# MainBoard.net
KiCad netlist of a schematic drawn in Altium Designer
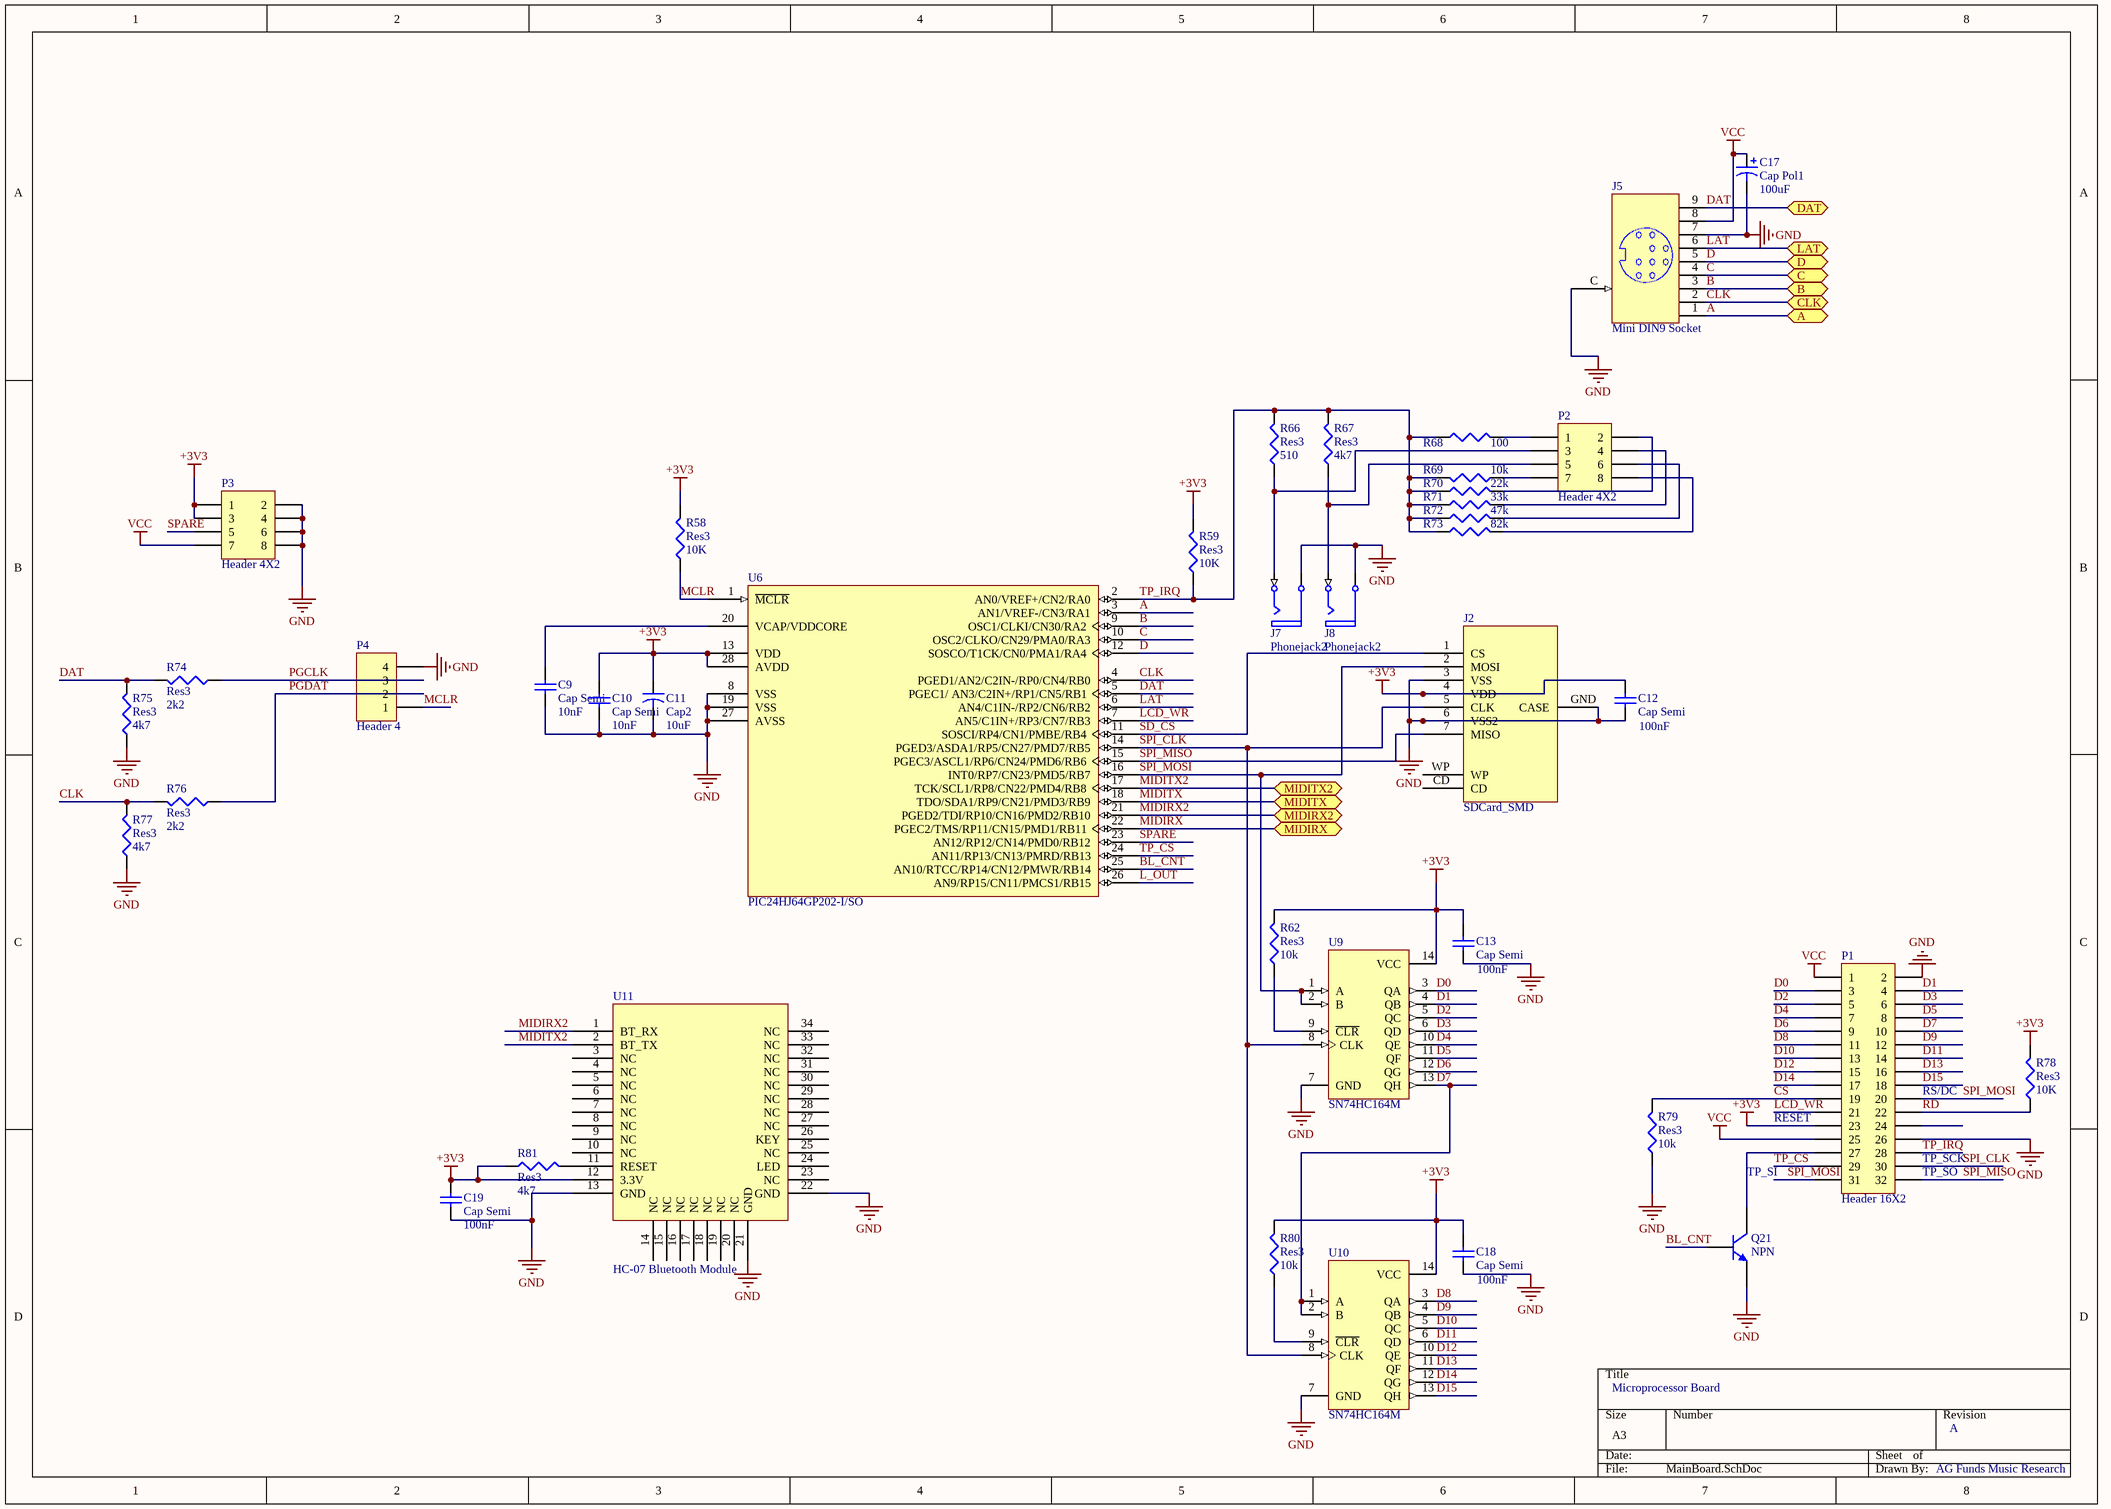
[diagram p0: MainBoard.SchDoc]

(export (version "E")
  (design (tool "Eeschema 10.0.6"))
  (components
    (comp (ref "C9")
      (value "Cap Semi")
      (footprint "1608[0603]")
      (description "Capacitor (Semiconductor SIM Model)")
      (fields (field (name "ALTIUM_VALUE") "10nF") (field (name "PUBLISHER") "Altium Limited"))
      (libsource (lib "Miscellaneous Devices") (part "Cap Semi"))
    )
    (comp (ref "C10")
      (value "Cap Semi")
      (footprint "1608[0603]")
      (description "Capacitor (Semiconductor SIM Model)")
      (fields (field (name "ALTIUM_VALUE") "10nF") (field (name "PUBLISHER") "Altium Limited"))
      (libsource (lib "Miscellaneous Devices") (part "Cap Semi"))
    )
    (comp (ref "C11")
      (value "Cap2")
      (footprint "CAPR5-4X5")
      (description "Capacitor")
      (fields (field (name "ALTIUM_VALUE") "10uF") (field (name "PUBLISHER") "Altium Limited"))
      (libsource (lib "Miscellaneous Devices") (part "Cap2"))
    )
    (comp (ref "C12")
      (value "Cap Semi")
      (footprint "1608[0603]")
      (description "Capacitor (Semiconductor SIM Model)")
      (fields (field (name "ALTIUM_VALUE") "100nF") (field (name "PUBLISHER") "Altium Limited"))
      (libsource (lib "Miscellaneous Devices") (part "Cap Semi"))
    )
    (comp (ref "C13")
      (value "Cap Semi")
      (footprint "1608[0603]")
      (description "Capacitor (Semiconductor SIM Model)")
      (fields (field (name "ALTIUM_VALUE") "100nF") (field (name "PUBLISHER") "Altium Limited"))
      (libsource (lib "Miscellaneous Devices") (part "Cap Semi"))
    )
    (comp (ref "C17")
      (value "Cap Pol1")
      (footprint "RB7.6-15")
      (description "Polarized Capacitor (Radial)")
      (fields (field (name "ALTIUM_VALUE") "100uF") (field (name "PUBLISHER") "Altium Limited"))
      (libsource (lib "Miscellaneous Devices") (part "Cap Pol1"))
    )
    (comp (ref "C18")
      (value "Cap Semi")
      (footprint "1608[0603]")
      (description "Capacitor (Semiconductor SIM Model)")
      (fields (field (name "ALTIUM_VALUE") "100nF") (field (name "PUBLISHER") "Altium Limited"))
      (libsource (lib "Miscellaneous Devices") (part "Cap Semi"))
    )
    (comp (ref "C19")
      (value "Cap Semi")
      (footprint "1608[0603]")
      (description "Capacitor (Semiconductor SIM Model)")
      (fields (field (name "ALTIUM_VALUE") "100nF") (field (name "PUBLISHER") "Altium Limited"))
      (libsource (lib "Miscellaneous Devices") (part "Cap Semi"))
    )
    (comp (ref "J2")
      (value "SDCard_SMD")
      (footprint "SDCard")
      (description "(101-00313) SD-Card Socket Surface Mount Amphenol Shouhmin Industry")
      (libsource (lib "MIDIPiano_7") (part "SDCard_SPI"))
    )
    (comp (ref "J5")
      (value "Mini DIN9 Socket")
      (footprint "RGBLED:9miniDIN")
      (description "CUI Inc. MD-90S MINIDIN9 PCB Mount Socket")
      (fields (field (name "PUBLISHER") "Altium Limited"))
      (libsource (lib "MIDIPiano_7") (part "mDIN9"))
    )
    (comp (ref "J7")
      (value "Phonejack2")
      (footprint "RN111PC")
      (description "Switchcraft RN-111PC Jack Socket, 1/4\" [6.5mm], Thru-Hole, 2-Conductor Open Circuit")
      (fields (field (name "PUBLISHER") "Altium Limited"))
      (libsource (lib "MIDIPiano_7") (part "Phonejack2"))
    )
    (comp (ref "J8")
      (value "Phonejack2")
      (footprint "RN111PC")
      (description "Switchcraft RN-111PC Jack Socket, 1/4\" [6.5mm], Thru-Hole, 2-Conductor Open Circuit")
      (fields (field (name "PUBLISHER") "Altium Limited"))
      (libsource (lib "MIDIPiano_7") (part "Phonejack2"))
    )
    (comp (ref "P1")
      (value "Header 16X2")
      (footprint "HDR2X16")
      (description "Header, 16-Pin, Dual row")
      (fields (field (name "PUBLISHER") "Altium Limited"))
      (libsource (lib "Miscellaneous Connectors") (part "Header 16X2"))
    )
    (comp (ref "P2")
      (value "Header 4X2")
      (footprint "HDR2X4")
      (description "Header, 4-Pin, Dual row")
      (fields (field (name "PUBLISHER") "Altium Limited"))
      (libsource (lib "MIDIPiano_7") (part "Header 4X2"))
    )
    (comp (ref "P3")
      (value "Header 4X2")
      (footprint "HDR2X4")
      (description "Header, 4-Pin, Dual row")
      (fields (field (name "PUBLISHER") "Altium Limited"))
      (libsource (lib "MIDIPiano_7") (part "Header 4X2"))
    )
    (comp (ref "P4")
      (value "Header 4")
      (footprint "HDR1X4")
      (description "Header, 4-Pin")
      (fields (field (name "PUBLISHER") "Altium Limited"))
      (libsource (lib "Miscellaneous Connectors") (part "Header 4"))
    )
    (comp (ref "Q21")
      (value "NPN")
      (footprint "SOT95P230-3N")
      (description "BC817/BC818 SMD NPN Bipolar Transistor")
      (fields (field (name "PUBLISHER") "Altium Limited"))
      (libsource (lib "MIDIPiano_7") (part "NPN"))
    )
    (comp (ref "R58")
      (value "Res3")
      (footprint "J1-0603")
      (description "Resistor")
      (fields (field (name "ALTIUM_VALUE") "10K") (field (name "PUBLISHER") "Altium Limited"))
      (libsource (lib "Miscellaneous Devices") (part "Res3"))
    )
    (comp (ref "R59")
      (value "Res3")
      (footprint "J1-0603")
      (description "Resistor")
      (fields (field (name "ALTIUM_VALUE") "10K") (field (name "PUBLISHER") "Altium Limited"))
      (libsource (lib "Miscellaneous Devices") (part "Res3"))
    )
    (comp (ref "R62")
      (value "Res3")
      (footprint "J1-0603")
      (description "Resistor")
      (fields (field (name "ALTIUM_VALUE") "10k") (field (name "PUBLISHER") "Altium Limited"))
      (libsource (lib "Miscellaneous Devices") (part "Res3"))
    )
    (comp (ref "R66")
      (value "Res3")
      (footprint "J1-0603")
      (description "Resistor")
      (fields (field (name "ALTIUM_VALUE") "510") (field (name "PUBLISHER") "Altium Limited"))
      (libsource (lib "Miscellaneous Devices") (part "Res3"))
    )
    (comp (ref "R67")
      (value "Res3")
      (footprint "J1-0603")
      (description "Resistor")
      (fields (field (name "ALTIUM_VALUE") "4k7") (field (name "PUBLISHER") "Altium Limited"))
      (libsource (lib "Miscellaneous Devices") (part "Res3"))
    )
    (comp (ref "R68")
      (value "100")
      (footprint "J1-0603")
      (description "Resistor")
      (fields (field (name "Comment") "Res3") (field (name "PUBLISHER") "Altium Limited"))
      (libsource (lib "Miscellaneous Devices") (part "Res3"))
    )
    (comp (ref "R69")
      (value "10k")
      (footprint "J1-0603")
      (description "Resistor")
      (fields (field (name "Comment") "Res3") (field (name "PUBLISHER") "Altium Limited"))
      (libsource (lib "Miscellaneous Devices") (part "Res3"))
    )
    (comp (ref "R70")
      (value "22k")
      (footprint "J1-0603")
      (description "Resistor")
      (fields (field (name "Comment") "Res3") (field (name "PUBLISHER") "Altium Limited"))
      (libsource (lib "Miscellaneous Devices") (part "Res3"))
    )
    (comp (ref "R71")
      (value "33k")
      (footprint "J1-0603")
      (description "Resistor")
      (fields (field (name "Comment") "Res3") (field (name "PUBLISHER") "Altium Limited"))
      (libsource (lib "Miscellaneous Devices") (part "Res3"))
    )
    (comp (ref "R72")
      (value "47k")
      (footprint "J1-0603")
      (description "Resistor")
      (fields (field (name "Comment") "Res3") (field (name "PUBLISHER") "Altium Limited"))
      (libsource (lib "Miscellaneous Devices") (part "Res3"))
    )
    (comp (ref "R73")
      (value "82k")
      (footprint "J1-0603")
      (description "Resistor")
      (fields (field (name "Comment") "Res3") (field (name "PUBLISHER") "Altium Limited"))
      (libsource (lib "Miscellaneous Devices") (part "Res3"))
    )
    (comp (ref "R74")
      (value "Res3")
      (footprint "J1-0603")
      (description "Resistor")
      (fields (field (name "ALTIUM_VALUE") "2k2") (field (name "PUBLISHER") "Altium Limited"))
      (libsource (lib "Miscellaneous Devices") (part "Res3"))
    )
    (comp (ref "R75")
      (value "Res3")
      (footprint "J1-0603")
      (description "Resistor")
      (fields (field (name "ALTIUM_VALUE") "4k7") (field (name "PUBLISHER") "Altium Limited"))
      (libsource (lib "Miscellaneous Devices") (part "Res3"))
    )
    (comp (ref "R76")
      (value "Res3")
      (footprint "J1-0603")
      (description "Resistor")
      (fields (field (name "ALTIUM_VALUE") "2k2") (field (name "PUBLISHER") "Altium Limited"))
      (libsource (lib "Miscellaneous Devices") (part "Res3"))
    )
    (comp (ref "R77")
      (value "Res3")
      (footprint "J1-0603")
      (description "Resistor")
      (fields (field (name "ALTIUM_VALUE") "4k7") (field (name "PUBLISHER") "Altium Limited"))
      (libsource (lib "Miscellaneous Devices") (part "Res3"))
    )
    (comp (ref "R78")
      (value "Res3")
      (footprint "J1-0603")
      (description "Resistor")
      (fields (field (name "ALTIUM_VALUE") "10K") (field (name "PUBLISHER") "Altium Limited"))
      (libsource (lib "Miscellaneous Devices") (part "Res3"))
    )
    (comp (ref "R79")
      (value "Res3")
      (footprint "J1-0603")
      (description "Resistor")
      (fields (field (name "ALTIUM_VALUE") "10k") (field (name "PUBLISHER") "Altium Limited"))
      (libsource (lib "Miscellaneous Devices") (part "Res3"))
    )
    (comp (ref "R80")
      (value "Res3")
      (footprint "J1-0603")
      (description "Resistor")
      (fields (field (name "ALTIUM_VALUE") "10k") (field (name "PUBLISHER") "Altium Limited"))
      (libsource (lib "Miscellaneous Devices") (part "Res3"))
    )
    (comp (ref "R81")
      (value "Res3")
      (footprint "J1-0603")
      (description "Resistor")
      (fields (field (name "ALTIUM_VALUE") "4k7") (field (name "PUBLISHER") "Altium Limited"))
      (libsource (lib "Miscellaneous Devices") (part "Res3"))
    )
    (comp (ref "U6")
      (value "PIC24HJ64GP202-I/SO")
      (footprint "SOIC-SO28_N")
      (fields (field (name "PUBLISHER") "Altium Limited"))
      (libsource (lib "Microchip Microcontroller 16-Bit PIC24H") (part "PIC24HJ64GP202-I/SO"))
    )
    (comp (ref "U9")
      (value "SN74HC164M")
      (footprint "SOIC127P600-14AM")
      (description "8-Bit Parallel-Out Serial Shift Register")
      (fields (field (name "PUBLISHER") "Altium Limited"))
      (libsource (lib "MIDIPiano_1") (part "SN74HC164M"))
    )
    (comp (ref "U10")
      (value "SN74HC164M")
      (footprint "SOIC127P600-14AM")
      (description "8-Bit Parallel-Out Serial Shift Register")
      (fields (field (name "PUBLISHER") "Altium Limited"))
      (libsource (lib "MIDIPiano_1") (part "SN74HC164M"))
    )
    (comp (ref "U11")
      (value "HC-07 Bluetooth Module")
      (footprint "BTModule")
      (libsource (lib "MIDIPiano_7") (part "BTModule"))
    )
  )
  (nets
    (net (code "1") (name "+3V3") (class "Default")
      (node (ref "C10") (pin "2") (pinfunction "2_2") (pintype "passive"))
      (node (ref "C11") (pin "1") (pinfunction "1_1") (pintype "passive"))
      (node (ref "C12") (pin "2") (pinfunction "2_2") (pintype "passive"))
      (node (ref "C13") (pin "2") (pinfunction "2_2") (pintype "passive"))
      (node (ref "C18") (pin "2") (pinfunction "2_2") (pintype "passive"))
      (node (ref "C19") (pin "2") (pinfunction "2_2") (pintype "passive"))
      (node (ref "J2") (pin "4") (pinfunction "VDD_4") (pintype "passive"))
      (node (ref "P1") (pin "23") (pinfunction "23_23") (pintype "passive"))
      (node (ref "P3") (pin "1") (pinfunction "1_1") (pintype "passive"))
      (node (ref "P3") (pin "3") (pinfunction "3_3") (pintype "passive"))
      (node (ref "R58") (pin "2") (pinfunction "2_2") (pintype "passive"))
      (node (ref "R59") (pin "2") (pinfunction "2_2") (pintype "passive"))
      (node (ref "R62") (pin "2") (pinfunction "2_2") (pintype "passive"))
      (node (ref "R78") (pin "2") (pinfunction "2_2") (pintype "passive"))
      (node (ref "R80") (pin "2") (pinfunction "2_2") (pintype "passive"))
      (node (ref "R81") (pin "1") (pinfunction "1_1") (pintype "passive"))
      (node (ref "U10") (pin "14") (pinfunction "VCC_14") (pintype "power_in"))
      (node (ref "U11") (pin "12") (pinfunction "3.3V_12") (pintype "passive"))
      (node (ref "U6") (pin "13") (pinfunction "VDD_13") (pintype "power_in"))
      (node (ref "U6") (pin "28") (pinfunction "AVDD_28") (pintype "power_in"))
      (node (ref "U9") (pin "14") (pinfunction "VCC_14") (pintype "power_in"))
    )
    (net (code "2") (name "/A") (class "Default")
      (node (ref "J5") (pin "1") (pinfunction "1_1") (pintype "passive"))
      (node (ref "U6") (pin "3") (pinfunction "AN1/VREF-/CN3/RA1_3") (pintype "bidirectional"))
    )
    (net (code "3") (name "/B") (class "Default")
      (node (ref "J5") (pin "3") (pinfunction "3_3") (pintype "passive"))
      (node (ref "U6") (pin "9") (pinfunction "OSC1/CLKI/CN30/RA2_9") (pintype "bidirectional"))
    )
    (net (code "4") (name "/BL_CNT") (class "Default")
      (node (ref "Q21") (pin "2") (pinfunction "B_2") (pintype "passive"))
      (node (ref "U6") (pin "25") (pinfunction "AN10/RTCC/RP14/CN12/PMWR/RB14_25") (pintype "bidirectional"))
    )
    (net (code "5") (name "/C") (class "Default")
      (node (ref "J5") (pin "4") (pinfunction "4_4") (pintype "passive"))
      (node (ref "U6") (pin "10") (pinfunction "OSC2/CLKO/CN29/PMA0/RA3_10") (pintype "bidirectional"))
    )
    (net (code "6") (name "/CLK") (class "Default")
      (node (ref "J5") (pin "2") (pinfunction "2_2") (pintype "passive"))
      (node (ref "R76") (pin "2") (pinfunction "2_2") (pintype "passive"))
      (node (ref "R77") (pin "2") (pinfunction "2_2") (pintype "passive"))
      (node (ref "U6") (pin "4") (pinfunction "PGED1/AN2/C2IN-/RP0/CN4/RB0_4") (pintype "bidirectional"))
    )
    (net (code "7") (name "/CS") (class "Default")
      (node (ref "P1") (pin "19") (pinfunction "19_19") (pintype "passive"))
      (node (ref "R79") (pin "2") (pinfunction "2_2") (pintype "passive"))
    )
    (net (code "8") (name "/D") (class "Default")
      (node (ref "J5") (pin "5") (pinfunction "5_5") (pintype "passive"))
      (node (ref "U6") (pin "12") (pinfunction "SOSCO/T1CK/CN0/PMA1/RA4_12") (pintype "bidirectional"))
    )
    (net (code "9") (name "/D0") (class "Default")
      (node (ref "P1") (pin "3") (pinfunction "3_3") (pintype "passive"))
      (node (ref "U9") (pin "3") (pinfunction "QA_3") (pintype "output"))
    )
    (net (code "10") (name "/D1") (class "Default")
      (node (ref "P1") (pin "4") (pinfunction "4_4") (pintype "passive"))
      (node (ref "U9") (pin "4") (pinfunction "QB_4") (pintype "output"))
    )
    (net (code "11") (name "/D2") (class "Default")
      (node (ref "P1") (pin "5") (pinfunction "5_5") (pintype "passive"))
      (node (ref "U9") (pin "5") (pinfunction "QC_5") (pintype "output"))
    )
    (net (code "12") (name "/D3") (class "Default")
      (node (ref "P1") (pin "6") (pinfunction "6_6") (pintype "passive"))
      (node (ref "U9") (pin "6") (pinfunction "QD_6") (pintype "output"))
    )
    (net (code "13") (name "/D4") (class "Default")
      (node (ref "P1") (pin "7") (pinfunction "7_7") (pintype "passive"))
      (node (ref "U9") (pin "10") (pinfunction "QE_10") (pintype "output"))
    )
    (net (code "14") (name "/D5") (class "Default")
      (node (ref "P1") (pin "8") (pinfunction "8_8") (pintype "passive"))
      (node (ref "U9") (pin "11") (pinfunction "QF_11") (pintype "output"))
    )
    (net (code "15") (name "/D6") (class "Default")
      (node (ref "P1") (pin "9") (pinfunction "9_9") (pintype "passive"))
      (node (ref "U9") (pin "12") (pinfunction "QG_12") (pintype "output"))
    )
    (net (code "16") (name "/D7") (class "Default")
      (node (ref "P1") (pin "10") (pinfunction "10_10") (pintype "passive"))
      (node (ref "U10") (pin "1") (pinfunction "A_1") (pintype "input"))
      (node (ref "U10") (pin "2") (pinfunction "B_2") (pintype "input"))
      (node (ref "U9") (pin "13") (pinfunction "QH_13") (pintype "output"))
    )
    (net (code "17") (name "/D8") (class "Default")
      (node (ref "P1") (pin "11") (pinfunction "11_11") (pintype "passive"))
      (node (ref "U10") (pin "3") (pinfunction "QA_3") (pintype "output"))
    )
    (net (code "18") (name "/D9") (class "Default")
      (node (ref "P1") (pin "12") (pinfunction "12_12") (pintype "passive"))
      (node (ref "U10") (pin "4") (pinfunction "QB_4") (pintype "output"))
    )
    (net (code "19") (name "/D10") (class "Default")
      (node (ref "P1") (pin "13") (pinfunction "13_13") (pintype "passive"))
      (node (ref "U10") (pin "5") (pinfunction "QC_5") (pintype "output"))
    )
    (net (code "20") (name "/D11") (class "Default")
      (node (ref "P1") (pin "14") (pinfunction "14_14") (pintype "passive"))
      (node (ref "U10") (pin "6") (pinfunction "QD_6") (pintype "output"))
    )
    (net (code "21") (name "/D12") (class "Default")
      (node (ref "P1") (pin "15") (pinfunction "15_15") (pintype "passive"))
      (node (ref "U10") (pin "10") (pinfunction "QE_10") (pintype "output"))
    )
    (net (code "22") (name "/D13") (class "Default")
      (node (ref "P1") (pin "16") (pinfunction "16_16") (pintype "passive"))
      (node (ref "U10") (pin "11") (pinfunction "QF_11") (pintype "output"))
    )
    (net (code "23") (name "/D14") (class "Default")
      (node (ref "P1") (pin "17") (pinfunction "17_17") (pintype "passive"))
      (node (ref "U10") (pin "12") (pinfunction "QG_12") (pintype "output"))
    )
    (net (code "24") (name "/D15") (class "Default")
      (node (ref "P1") (pin "18") (pinfunction "18_18") (pintype "passive"))
      (node (ref "U10") (pin "13") (pinfunction "QH_13") (pintype "output"))
    )
    (net (code "25") (name "/DAT") (class "Default")
      (node (ref "J5") (pin "9") (pinfunction "9_9") (pintype "passive"))
      (node (ref "R74") (pin "2") (pinfunction "2_2") (pintype "passive"))
      (node (ref "R75") (pin "2") (pinfunction "2_2") (pintype "passive"))
      (node (ref "U6") (pin "5") (pinfunction "PGEC1/_AN3/C2IN+/RP1/CN5/RB1_5") (pintype "bidirectional"))
    )
    (net (code "26") (name "/LAT") (class "Default")
      (node (ref "J5") (pin "6") (pinfunction "6_6") (pintype "passive"))
      (node (ref "U6") (pin "6") (pinfunction "AN4/C1IN-/RP2/CN6/RB2_6") (pintype "bidirectional"))
    )
    (net (code "27") (name "/LCD_WR") (class "Default")
      (node (ref "P1") (pin "21") (pinfunction "21_21") (pintype "passive"))
      (node (ref "U6") (pin "7") (pinfunction "AN5/C1IN+/RP3/CN7/RB3_7") (pintype "bidirectional"))
    )
    (net (code "28") (name "/L_OUT") (class "Default")
      (node (ref "U6") (pin "26") (pinfunction "AN9/RP15/CN11/PMCS1/RB15_26") (pintype "bidirectional"))
    )
    (net (code "29") (name "/MCLR") (class "Default")
      (node (ref "P4") (pin "1") (pinfunction "1_1") (pintype "passive"))
      (node (ref "R58") (pin "1") (pinfunction "1_1") (pintype "passive"))
      (node (ref "U6") (pin "1") (pinfunction "~{MCLR}_1") (pintype "input"))
    )
    (net (code "30") (name "/MIDIRX") (class "Default")
      (node (ref "U6") (pin "22") (pinfunction "PGEC2/TMS/RP11/CN15/PMD1/RB11_22") (pintype "bidirectional"))
    )
    (net (code "31") (name "/MIDIRX2") (class "Default")
      (node (ref "U11") (pin "1") (pinfunction "BT_RX_1") (pintype "passive"))
      (node (ref "U6") (pin "21") (pinfunction "PGED2/TDI/RP10/CN16/PMD2/RB10_21") (pintype "bidirectional"))
    )
    (net (code "32") (name "/MIDITX") (class "Default")
      (node (ref "U6") (pin "18") (pinfunction "TDO/SDA1/RP9/CN21/PMD3/RB9_18") (pintype "bidirectional"))
    )
    (net (code "33") (name "/MIDITX2") (class "Default")
      (node (ref "U11") (pin "2") (pinfunction "BT_TX_2") (pintype "passive"))
      (node (ref "U6") (pin "17") (pinfunction "TCK/SCL1/RP8/CN22/PMD4/RB8_17") (pintype "bidirectional"))
    )
    (net (code "34") (name "/PGCLK") (class "Default")
      (node (ref "P4") (pin "3") (pinfunction "3_3") (pintype "passive"))
      (node (ref "R74") (pin "1") (pinfunction "1_1") (pintype "passive"))
    )
    (net (code "35") (name "/PGDAT") (class "Default")
      (node (ref "P4") (pin "2") (pinfunction "2_2") (pintype "passive"))
      (node (ref "R76") (pin "1") (pinfunction "1_1") (pintype "passive"))
    )
    (net (code "36") (name "/RD") (class "Default")
      (node (ref "P1") (pin "22") (pinfunction "22_22") (pintype "passive"))
      (node (ref "R78") (pin "1") (pinfunction "1_1") (pintype "passive"))
    )
    (net (code "37") (name "/SD_CS") (class "Default")
      (node (ref "J2") (pin "1") (pinfunction "CS_1") (pintype "passive"))
      (node (ref "U6") (pin "11") (pinfunction "SOSCI/RP4/CN1/PMBE/RB4_11") (pintype "bidirectional"))
    )
    (net (code "38") (name "/SPARE") (class "Default")
      (node (ref "P3") (pin "5") (pinfunction "5_5") (pintype "passive"))
      (node (ref "U6") (pin "23") (pinfunction "AN12/RP12/CN14/PMD0/RB12_23") (pintype "bidirectional"))
    )
    (net (code "39") (name "/SPI_CLK") (class "Default")
      (node (ref "J2") (pin "5") (pinfunction "CLK_5") (pintype "passive"))
      (node (ref "P1") (pin "30") (pinfunction "30_30") (pintype "passive"))
      (node (ref "U10") (pin "8") (pinfunction "CLK_8") (pintype "input"))
      (node (ref "U6") (pin "14") (pinfunction "PGED3/ASDA1/RP5/CN27/PMD7/RB5_14") (pintype "bidirectional"))
      (node (ref "U9") (pin "8") (pinfunction "CLK_8") (pintype "input"))
    )
    (net (code "40") (name "/SPI_MISO") (class "Default")
      (node (ref "J2") (pin "7") (pinfunction "MISO_7") (pintype "passive"))
      (node (ref "P1") (pin "32") (pinfunction "32_32") (pintype "passive"))
      (node (ref "U6") (pin "15") (pinfunction "PGEC3/ASCL1/RP6/CN24/PMD6/RB6_15") (pintype "bidirectional"))
    )
    (net (code "41") (name "/SPI_MOSI") (class "Default")
      (node (ref "J2") (pin "2") (pinfunction "MOSI_2") (pintype "passive"))
      (node (ref "P1") (pin "20") (pinfunction "20_20") (pintype "passive"))
      (node (ref "P1") (pin "31") (pinfunction "31_31") (pintype "passive"))
      (node (ref "U6") (pin "16") (pinfunction "INT0/RP7/CN23/PMD5/RB7_16") (pintype "bidirectional"))
      (node (ref "U9") (pin "1") (pinfunction "A_1") (pintype "input"))
      (node (ref "U9") (pin "2") (pinfunction "B_2") (pintype "input"))
    )
    (net (code "42") (name "/TP_CS") (class "Default")
      (node (ref "P1") (pin "29") (pinfunction "29_29") (pintype "passive"))
      (node (ref "U6") (pin "24") (pinfunction "AN11/RP13/CN13/PMRD/RB13_24") (pintype "bidirectional"))
    )
    (net (code "43") (name "/TP_IRQ") (class "Default")
      (node (ref "P1") (pin "28") (pinfunction "28_28") (pintype "passive"))
      (node (ref "R59") (pin "1") (pinfunction "1_1") (pintype "passive"))
      (node (ref "R66") (pin "2") (pinfunction "2_2") (pintype "passive"))
      (node (ref "R67") (pin "2") (pinfunction "2_2") (pintype "passive"))
      (node (ref "R68") (pin "1") (pinfunction "1_1") (pintype "passive"))
      (node (ref "R69") (pin "2") (pinfunction "2_2") (pintype "passive"))
      (node (ref "R70") (pin "1") (pinfunction "1_1") (pintype "passive"))
      (node (ref "R71") (pin "1") (pinfunction "1_1") (pintype "passive"))
      (node (ref "R72") (pin "1") (pinfunction "1_1") (pintype "passive"))
      (node (ref "R73") (pin "1") (pinfunction "1_1") (pintype "passive"))
      (node (ref "U6") (pin "2") (pinfunction "AN0/VREF+/CN2/RA0_2") (pintype "bidirectional"))
    )
    (net (code "44") (name "GND") (class "Default")
      (node (ref "C10") (pin "1") (pinfunction "1_1") (pintype "passive"))
      (node (ref "C11") (pin "2") (pinfunction "2_2") (pintype "passive"))
      (node (ref "C12") (pin "1") (pinfunction "1_1") (pintype "passive"))
      (node (ref "C13") (pin "1") (pinfunction "1_1") (pintype "passive"))
      (node (ref "C17") (pin "2") (pinfunction "2_2") (pintype "passive"))
      (node (ref "C18") (pin "1") (pinfunction "1_1") (pintype "passive"))
      (node (ref "C19") (pin "1") (pinfunction "1_1") (pintype "passive"))
      (node (ref "C9") (pin "1") (pinfunction "1_1") (pintype "passive"))
      (node (ref "J2") (pin "3") (pinfunction "VSS_3") (pintype "passive"))
      (node (ref "J2") (pin "6") (pinfunction "VSS2_6") (pintype "passive"))
      (node (ref "J2") (pin "GND") (pinfunction "CASE_GND") (pintype "passive"))
      (node (ref "J5") (pin "7") (pinfunction "7_7") (pintype "passive"))
      (node (ref "J5") (pin "C") (pinfunction "C_C") (pintype "input"))
      (node (ref "J7") (pin "SLEEVE") (pinfunction "S_SLEEVE") (pintype "power_in"))
      (node (ref "J8") (pin "SLEEVE") (pinfunction "S_SLEEVE") (pintype "power_in"))
      (node (ref "P1") (pin "2") (pinfunction "2_2") (pintype "passive"))
      (node (ref "P1") (pin "26") (pinfunction "26_26") (pintype "passive"))
      (node (ref "P3") (pin "2") (pinfunction "2_2") (pintype "passive"))
      (node (ref "P3") (pin "4") (pinfunction "4_4") (pintype "passive"))
      (node (ref "P3") (pin "6") (pinfunction "6_6") (pintype "passive"))
      (node (ref "P3") (pin "8") (pinfunction "8_8") (pintype "passive"))
      (node (ref "P4") (pin "4") (pinfunction "4_4") (pintype "passive"))
      (node (ref "Q21") (pin "3") (pinfunction "E_3") (pintype "passive"))
      (node (ref "R75") (pin "1") (pinfunction "1_1") (pintype "passive"))
      (node (ref "R77") (pin "1") (pinfunction "1_1") (pintype "passive"))
      (node (ref "R79") (pin "1") (pinfunction "1_1") (pintype "passive"))
      (node (ref "U10") (pin "7") (pinfunction "GND_7") (pintype "power_in"))
      (node (ref "U11") (pin "13") (pinfunction "GND_13") (pintype "passive"))
      (node (ref "U11") (pin "21") (pinfunction "GND_21") (pintype "passive"))
      (node (ref "U11") (pin "22") (pinfunction "GND_22") (pintype "passive"))
      (node (ref "U6") (pin "19") (pinfunction "VSS_19") (pintype "power_in"))
      (node (ref "U6") (pin "27") (pinfunction "AVSS_27") (pintype "power_in"))
      (node (ref "U6") (pin "8") (pinfunction "VSS_8") (pintype "power_in"))
      (node (ref "U9") (pin "7") (pinfunction "GND_7") (pintype "power_in"))
    )
    (net (code "45") (name "Net-(J7-T)") (class "Default")
      (node (ref "J7") (pin "TIP") (pinfunction "T_TIP") (pintype "input"))
      (node (ref "P2") (pin "3") (pinfunction "3_3") (pintype "passive"))
      (node (ref "R66") (pin "1") (pinfunction "1_1") (pintype "passive"))
    )
    (net (code "46") (name "Net-(J8-T)") (class "Default")
      (node (ref "J8") (pin "TIP") (pinfunction "T_TIP") (pintype "input"))
      (node (ref "P2") (pin "5") (pinfunction "5_5") (pintype "passive"))
      (node (ref "R67") (pin "1") (pinfunction "1_1") (pintype "passive"))
    )
    (net (code "47") (name "Net-(P2-Pad1)") (class "Default")
      (node (ref "P2") (pin "1") (pinfunction "1_1") (pintype "passive"))
      (node (ref "R68") (pin "2") (pinfunction "2_2") (pintype "passive"))
    )
    (net (code "48") (name "Net-(P2-Pad2)") (class "Default")
      (node (ref "P2") (pin "2") (pinfunction "2_2") (pintype "passive"))
      (node (ref "R70") (pin "2") (pinfunction "2_2") (pintype "passive"))
    )
    (net (code "49") (name "Net-(P2-Pad4)") (class "Default")
      (node (ref "P2") (pin "4") (pinfunction "4_4") (pintype "passive"))
      (node (ref "R71") (pin "2") (pinfunction "2_2") (pintype "passive"))
    )
    (net (code "50") (name "Net-(P2-Pad6)") (class "Default")
      (node (ref "P2") (pin "6") (pinfunction "6_6") (pintype "passive"))
      (node (ref "R72") (pin "2") (pinfunction "2_2") (pintype "passive"))
    )
    (net (code "51") (name "Net-(P2-Pad7)") (class "Default")
      (node (ref "P2") (pin "7") (pinfunction "7_7") (pintype "passive"))
      (node (ref "R69") (pin "1") (pinfunction "1_1") (pintype "passive"))
    )
    (net (code "52") (name "Net-(P2-Pad8)") (class "Default")
      (node (ref "P2") (pin "8") (pinfunction "8_8") (pintype "passive"))
      (node (ref "R73") (pin "2") (pinfunction "2_2") (pintype "passive"))
    )
    (net (code "53") (name "Net-(Q21-C)") (class "Default")
      (node (ref "P1") (pin "27") (pinfunction "27_27") (pintype "passive"))
      (node (ref "Q21") (pin "1") (pinfunction "C_1") (pintype "passive"))
    )
    (net (code "54") (name "Net-(U6-VCAP{slash}VDDCORE)") (class "Default")
      (node (ref "C9") (pin "2") (pinfunction "2_2") (pintype "passive"))
      (node (ref "U6") (pin "20") (pinfunction "VCAP/VDDCORE_20") (pintype "power_in"))
    )
    (net (code "55") (name "Net-(U9-~{CLR})") (class "Default")
      (node (ref "R62") (pin "1") (pinfunction "1_1") (pintype "passive"))
      (node (ref "U9") (pin "9") (pinfunction "~{CLR}_9") (pintype "input"))
    )
    (net (code "56") (name "Net-(U10-~{CLR})") (class "Default")
      (node (ref "R80") (pin "1") (pinfunction "1_1") (pintype "passive"))
      (node (ref "U10") (pin "9") (pinfunction "~{CLR}_9") (pintype "input"))
    )
    (net (code "57") (name "Net-(U11-RESET)") (class "Default")
      (node (ref "R81") (pin "2") (pinfunction "2_2") (pintype "passive"))
      (node (ref "U11") (pin "11") (pinfunction "RESET_11") (pintype "passive"))
    )
    (net (code "58") (name "VCC") (class "Default")
      (node (ref "C17") (pin "1") (pinfunction "1_1") (pintype "passive"))
      (node (ref "J5") (pin "8") (pinfunction "8_8") (pintype "passive"))
      (node (ref "P1") (pin "1") (pinfunction "1_1") (pintype "passive"))
      (node (ref "P1") (pin "25") (pinfunction "25_25") (pintype "passive"))
      (node (ref "P3") (pin "7") (pinfunction "7_7") (pintype "passive"))
    )
    (net (code "59") (name "unconnected-(J2-PadCD)") (class "Default")
      (node (ref "J2") (pin "CD") (pinfunction "CD_CD") (pintype "passive"))
    )
    (net (code "60") (name "unconnected-(J2-PadWP)") (class "Default")
      (node (ref "J2") (pin "WP") (pinfunction "WP_WP") (pintype "passive"))
    )
    (net (code "61") (name "unconnected-(P1-Pad24)") (class "Default")
      (node (ref "P1") (pin "24") (pinfunction "24_24") (pintype "passive"))
    )
    (net (code "62") (name "unconnected-(U11-KEY-Pad26)") (class "Default")
      (node (ref "U11") (pin "26") (pinfunction "KEY_26") (pintype "passive"))
    )
    (net (code "63") (name "unconnected-(U11-LED-Pad24)") (class "Default")
      (node (ref "U11") (pin "24") (pinfunction "LED_24") (pintype "passive"))
    )
    (net (code "64") (name "unconnected-(U11-NC-Pad3)") (class "Default")
      (node (ref "U11") (pin "3") (pinfunction "NC_3") (pintype "passive"))
    )
    (net (code "65") (name "unconnected-(U11-NC-Pad4)") (class "Default")
      (node (ref "U11") (pin "4") (pinfunction "NC_4") (pintype "passive"))
    )
    (net (code "66") (name "unconnected-(U11-NC-Pad5)") (class "Default")
      (node (ref "U11") (pin "5") (pinfunction "NC_5") (pintype "passive"))
    )
    (net (code "67") (name "unconnected-(U11-NC-Pad6)") (class "Default")
      (node (ref "U11") (pin "6") (pinfunction "NC_6") (pintype "passive"))
    )
    (net (code "68") (name "unconnected-(U11-NC-Pad7)") (class "Default")
      (node (ref "U11") (pin "7") (pinfunction "NC_7") (pintype "passive"))
    )
    (net (code "69") (name "unconnected-(U11-NC-Pad8)") (class "Default")
      (node (ref "U11") (pin "8") (pinfunction "NC_8") (pintype "passive"))
    )
    (net (code "70") (name "unconnected-(U11-NC-Pad9)") (class "Default")
      (node (ref "U11") (pin "9") (pinfunction "NC_9") (pintype "passive"))
    )
    (net (code "71") (name "unconnected-(U11-NC-Pad10)") (class "Default")
      (node (ref "U11") (pin "10") (pinfunction "NC_10") (pintype "passive"))
    )
    (net (code "72") (name "unconnected-(U11-NC-Pad14)") (class "Default")
      (node (ref "U11") (pin "14") (pinfunction "NC_14") (pintype "passive"))
    )
    (net (code "73") (name "unconnected-(U11-NC-Pad15)") (class "Default")
      (node (ref "U11") (pin "15") (pinfunction "NC_15") (pintype "passive"))
    )
    (net (code "74") (name "unconnected-(U11-NC-Pad16)") (class "Default")
      (node (ref "U11") (pin "16") (pinfunction "NC_16") (pintype "passive"))
    )
    (net (code "75") (name "unconnected-(U11-NC-Pad17)") (class "Default")
      (node (ref "U11") (pin "17") (pinfunction "NC_17") (pintype "passive"))
    )
    (net (code "76") (name "unconnected-(U11-NC-Pad18)") (class "Default")
      (node (ref "U11") (pin "18") (pinfunction "NC_18") (pintype "passive"))
    )
    (net (code "77") (name "unconnected-(U11-NC-Pad19)") (class "Default")
      (node (ref "U11") (pin "19") (pinfunction "NC_19") (pintype "passive"))
    )
    (net (code "78") (name "unconnected-(U11-NC-Pad20)") (class "Default")
      (node (ref "U11") (pin "20") (pinfunction "NC_20") (pintype "passive"))
    )
    (net (code "79") (name "unconnected-(U11-NC-Pad23)") (class "Default")
      (node (ref "U11") (pin "23") (pinfunction "NC_23") (pintype "passive"))
    )
    (net (code "80") (name "unconnected-(U11-NC-Pad25)") (class "Default")
      (node (ref "U11") (pin "25") (pinfunction "NC_25") (pintype "passive"))
    )
    (net (code "81") (name "unconnected-(U11-NC-Pad27)") (class "Default")
      (node (ref "U11") (pin "27") (pinfunction "NC_27") (pintype "passive"))
    )
    (net (code "82") (name "unconnected-(U11-NC-Pad28)") (class "Default")
      (node (ref "U11") (pin "28") (pinfunction "NC_28") (pintype "passive"))
    )
    (net (code "83") (name "unconnected-(U11-NC-Pad29)") (class "Default")
      (node (ref "U11") (pin "29") (pinfunction "NC_29") (pintype "passive"))
    )
    (net (code "84") (name "unconnected-(U11-NC-Pad30)") (class "Default")
      (node (ref "U11") (pin "30") (pinfunction "NC_30") (pintype "passive"))
    )
    (net (code "85") (name "unconnected-(U11-NC-Pad31)") (class "Default")
      (node (ref "U11") (pin "31") (pinfunction "NC_31") (pintype "passive"))
    )
    (net (code "86") (name "unconnected-(U11-NC-Pad32)") (class "Default")
      (node (ref "U11") (pin "32") (pinfunction "NC_32") (pintype "passive"))
    )
    (net (code "87") (name "unconnected-(U11-NC-Pad33)") (class "Default")
      (node (ref "U11") (pin "33") (pinfunction "NC_33") (pintype "passive"))
    )
    (net (code "88") (name "unconnected-(U11-NC-Pad34)") (class "Default")
      (node (ref "U11") (pin "34") (pinfunction "NC_34") (pintype "passive"))
    )
  )
)
